# SX1308.net
KiCad netlist of a schematic drawn in Altium Designer
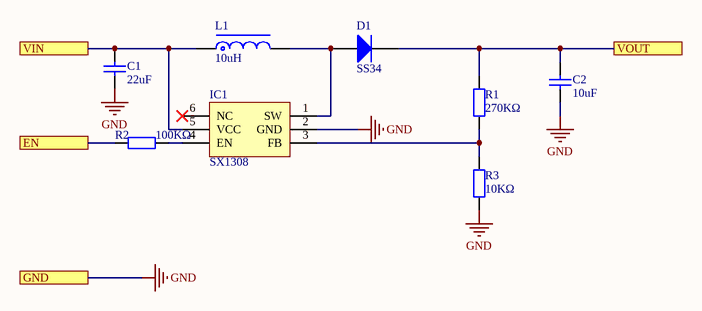
[diagram p0: SX1308.SchDoc]

(export (version "E")
  (design (tool "Eeschema 10.0.6"))
  (components
    (comp (ref "C1")
      (value "22uF")
      (footprint "LC-0805_C")
      (description "贴片电容")
      (libsource (lib "Miscellaneous Devices LC") (part "0805 22uF (226) 20% 25V"))
    )
    (comp (ref "C2")
      (value "10uF")
      (footprint "LC-1206_C")
      (description "贴片电容")
      (libsource (lib "Miscellaneous Devices LC") (part "1206 10uF (106) 10% 50V"))
    )
    (comp (ref "D1")
      (value "SS34")
      (footprint "LC-SMA(DO-214AC)_S1")
      (description "二极管")
      (libsource (lib "Miscellaneous Devices LC") (part "SMA(DO-214AC) SS54"))
    )
    (comp (ref "IC1")
      (value "SX1308")
      (footprint "SOT23-6N")
      (description "可调升压芯片")
      (fields (field (name "版权归属") "封装库来自淘宝 ID：黄晶宝石"))
      (libsource (lib "1.1 - 电源类芯片") (part "SX1308"))
    )
    (comp (ref "L1")
      (value "10uH")
      (footprint "CDRH73")
      (description "功率屏蔽电感")
      (fields (field (name "版权归属") "封装库来自淘宝 ID：黄晶宝石"))
      (libsource (lib "0.1 - 电阻-电容-电感") (part "L-CDRH"))
    )
    (comp (ref "R1")
      (value "270KΩ")
      (footprint "LC-0603_R")
      (description "贴片电阻")
      (libsource (lib "Miscellaneous Devices LC") (part "0603 390KΩ (3903) 1%"))
    )
    (comp (ref "R2")
      (value "100KΩ")
      (footprint "LC-0603_R")
      (description "贴片电阻")
      (libsource (lib "Miscellaneous Devices LC") (part "0603 100KΩ (1003) 1%"))
    )
    (comp (ref "R3")
      (value "10KΩ")
      (footprint "LC-0603_R")
      (description "贴片电阻")
      (libsource (lib "Miscellaneous Devices LC") (part "0603 10KΩ (1002) 1%"))
    )
  )
  (nets
    (net (code "1") (name "/EN") (class "Default")
      (node (ref "R2") (pin "1") (pinfunction "1_1") (pintype "passive"))
    )
    (net (code "2") (name "/VIN") (class "Default")
      (node (ref "C1") (pin "2") (pinfunction "2_2") (pintype "passive"))
      (node (ref "IC1") (pin "5") (pinfunction "VCC_5") (pintype "passive"))
      (node (ref "L1") (pin "1") (pinfunction "1_1") (pintype "passive"))
    )
    (net (code "3") (name "/VOUT") (class "Default")
      (node (ref "C2") (pin "2") (pinfunction "2_2") (pintype "passive"))
      (node (ref "D1") (pin "2") (pinfunction "K_2") (pintype "passive"))
      (node (ref "R1") (pin "2") (pinfunction "2_2") (pintype "passive"))
    )
    (net (code "4") (name "GND") (class "Default")
      (node (ref "C1") (pin "1") (pinfunction "1_1") (pintype "passive"))
      (node (ref "C2") (pin "1") (pinfunction "1_1") (pintype "passive"))
      (node (ref "IC1") (pin "2") (pinfunction "GND_2") (pintype "passive"))
      (node (ref "R3") (pin "1") (pinfunction "1_1") (pintype "passive"))
    )
    (net (code "5") (name "Net-(D1-A)") (class "Default")
      (node (ref "D1") (pin "1") (pinfunction "A_1") (pintype "passive"))
      (node (ref "IC1") (pin "1") (pinfunction "SW_1") (pintype "passive"))
      (node (ref "L1") (pin "2") (pinfunction "2_2") (pintype "passive"))
    )
    (net (code "6") (name "Net-(IC1-EN)") (class "Default")
      (node (ref "IC1") (pin "4") (pinfunction "EN_4") (pintype "passive"))
      (node (ref "R2") (pin "2") (pinfunction "2_2") (pintype "passive"))
    )
    (net (code "7") (name "Net-(IC1-FB)") (class "Default")
      (node (ref "IC1") (pin "3") (pinfunction "FB_3") (pintype "passive"))
      (node (ref "R1") (pin "1") (pinfunction "1_1") (pintype "passive"))
      (node (ref "R3") (pin "2") (pinfunction "2_2") (pintype "passive"))
    )
    (net (code "8") (name "unconnected-(IC1-NC-Pad6)") (class "Default")
      (node (ref "IC1") (pin "6") (pinfunction "NC_6") (pintype "passive+no_connect"))
    )
  )
)
